# ADS1298_2.net
KiCad netlist of a schematic drawn in Altium Designer
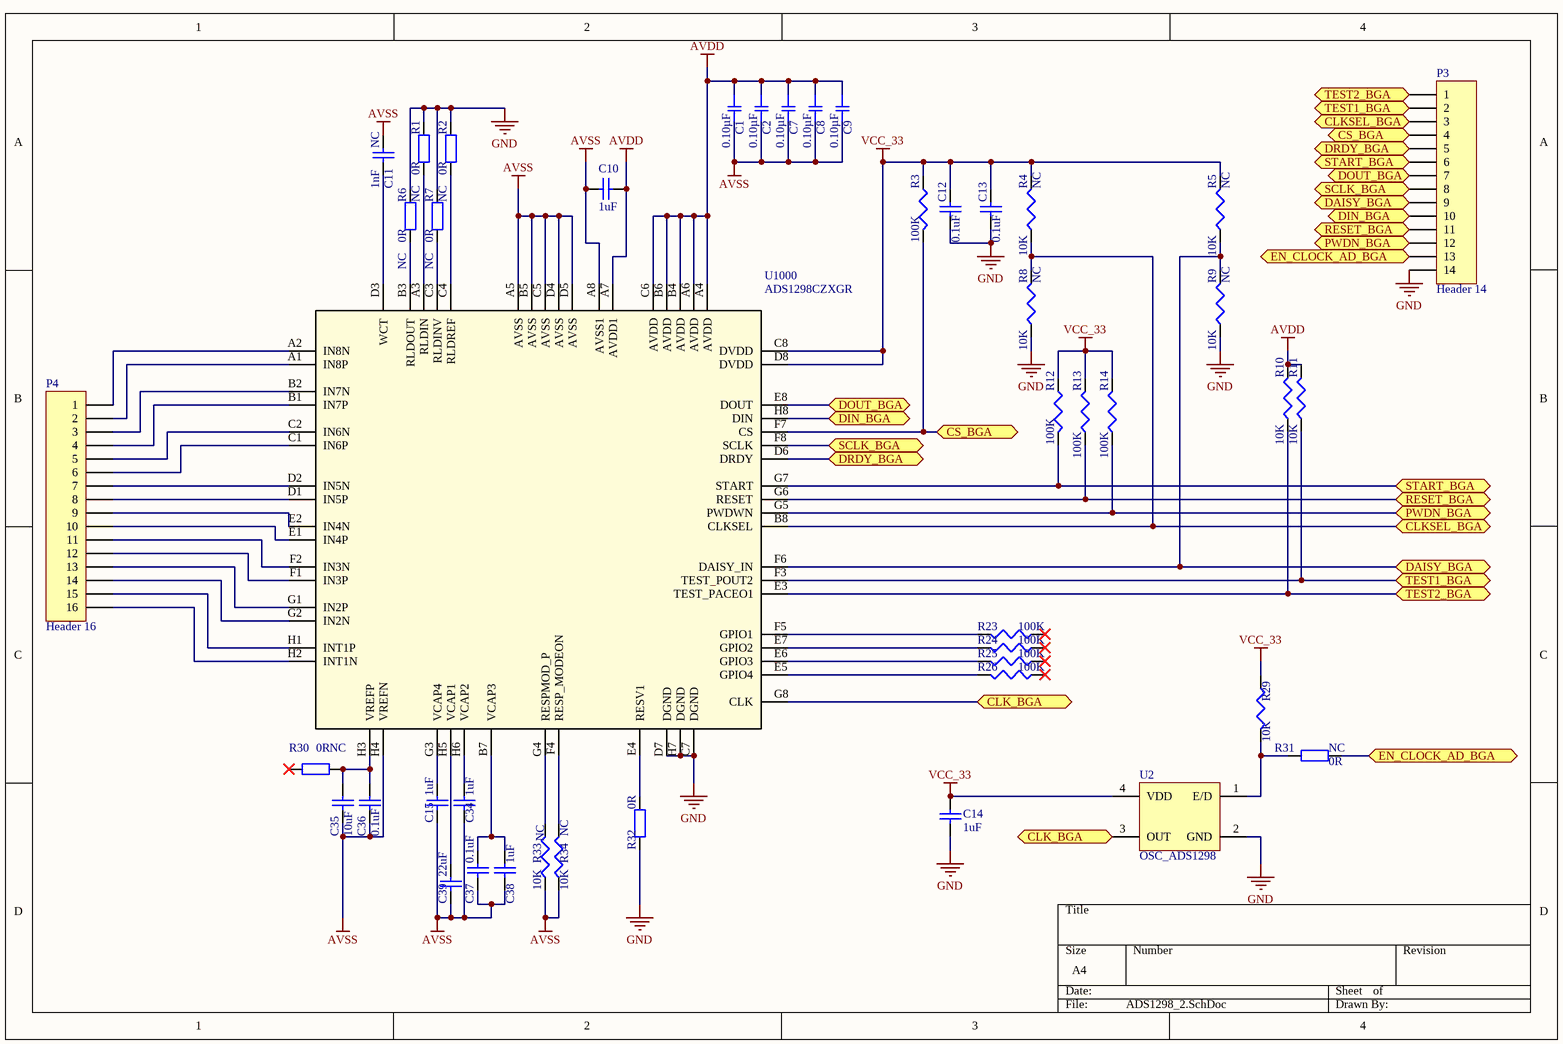
[diagram p0: ADS1298_2.SchDoc]

(export (version "E")
  (design (tool "Eeschema 10.0.6"))
  (components
    (comp (ref "C1")
      (value "0.10µF")
      (footprint "SMD-0201C")
      (description "CAP CER 0.1UF 10V X6S 0201")
      (fields
        (field (name "DIGI-KEY PART NUMBER") "490-12232-1-ND")
        (field (name "PART NUMBER") "GRT033C81A104KE01D")
      )
      (libsource (lib "capacitor_murata_0201") (part "GRT033C81A104KE01D"))
    )
    (comp (ref "C2")
      (value "0.10µF")
      (footprint "SMD-0201C")
      (description "CAP CER 0.1UF 10V X6S 0201")
      (fields
        (field (name "DIGI-KEY PART NUMBER") "490-12232-1-ND")
        (field (name "PART NUMBER") "GRT033C81A104KE01D")
      )
      (libsource (lib "capacitor_murata_0201") (part "GRT033C81A104KE01D"))
    )
    (comp (ref "C7")
      (value "0.10µF")
      (footprint "SMD-0201C")
      (description "CAP CER 0.1UF 10V X6S 0201")
      (fields
        (field (name "DIGI-KEY PART NUMBER") "490-12232-1-ND")
        (field (name "PART NUMBER") "GRT033C81A104KE01D")
      )
      (libsource (lib "capacitor_murata_0201") (part "GRT033C81A104KE01D"))
    )
    (comp (ref "C8")
      (value "0.10µF")
      (footprint "SMD-0201C")
      (description "CAP CER 0.1UF 10V X6S 0201")
      (fields
        (field (name "DIGI-KEY PART NUMBER") "490-12232-1-ND")
        (field (name "PART NUMBER") "GRT033C81A104KE01D")
      )
      (libsource (lib "capacitor_murata_0201") (part "GRT033C81A104KE01D"))
    )
    (comp (ref "C9")
      (value "0.10µF")
      (footprint "SMD-0201C")
      (description "CAP CER 0.1UF 10V X6S 0201")
      (fields
        (field (name "DIGI-KEY PART NUMBER") "490-12232-1-ND")
        (field (name "PART NUMBER") "GRT033C81A104KE01D")
      )
      (libsource (lib "capacitor_murata_0201") (part "GRT033C81A104KE01D"))
    )
    (comp (ref "C10")
      (value "1uF")
      (footprint "cap_0402_R - modified")
      (description "Capacitor")
      (fields (field (name "Comment") "Cap") (field (name "PUBLISHER") "Altium Limited"))
      (libsource (lib "Miscellaneous Devices") (part "Cap"))
    )
    (comp (ref "C11")
      (value "NC")
      (footprint "cap_0402_R - modified")
      (description "Capacitor")
      (fields (field (name "ALTIUM_VALUE") "1nF") (field (name "PUBLISHER") "Altium Limited"))
      (libsource (lib "Miscellaneous Devices") (part "Cap"))
    )
    (comp (ref "C12")
      (value "0.1uF")
      (footprint "cap_0402_R - modified")
      (description "Capacitor")
      (fields (field (name "Comment") "Cap") (field (name "PUBLISHER") "Altium Limited"))
      (libsource (lib "Miscellaneous Devices") (part "Cap"))
    )
    (comp (ref "C13")
      (value "0.1uF")
      (footprint "cap_0402_R - modified")
      (description "Capacitor")
      (fields (field (name "Comment") "Cap") (field (name "PUBLISHER") "Altium Limited"))
      (libsource (lib "Miscellaneous Devices") (part "Cap"))
    )
    (comp (ref "C14")
      (value "1uF")
      (footprint "cap_0402_R - modified")
      (description "Capacitor")
      (fields (field (name "Comment") "Cap") (field (name "PUBLISHER") "Altium Limited"))
      (libsource (lib "Miscellaneous Devices") (part "Cap"))
    )
    (comp (ref "C15")
      (value "1uF")
      (footprint "cap_0402_R - modified")
      (description "Capacitor")
      (fields (field (name "Comment") "Cap") (field (name "PUBLISHER") "Altium Limited"))
      (libsource (lib "Miscellaneous Devices") (part "Cap"))
    )
    (comp (ref "C34")
      (value "1uF")
      (footprint "cap_0402_R - modified")
      (description "Capacitor")
      (fields (field (name "Comment") "Cap") (field (name "PUBLISHER") "Altium Limited"))
      (libsource (lib "Miscellaneous Devices") (part "Cap"))
    )
    (comp (ref "C35")
      (value "10uF")
      (footprint "cap_0402_R - modified")
      (description "Capacitor")
      (fields (field (name "Comment") "Cap") (field (name "PUBLISHER") "Altium Limited"))
      (libsource (lib "Miscellaneous Devices") (part "Cap"))
    )
    (comp (ref "C36")
      (value "0.1uF")
      (footprint "cap_0402_R - modified")
      (description "Capacitor")
      (fields (field (name "Comment") "Cap") (field (name "PUBLISHER") "Altium Limited"))
      (libsource (lib "Miscellaneous Devices") (part "Cap"))
    )
    (comp (ref "C37")
      (value "0.1uF")
      (footprint "cap_0402_R - modified")
      (description "Capacitor")
      (fields (field (name "Comment") "Cap") (field (name "PUBLISHER") "Altium Limited"))
      (libsource (lib "Miscellaneous Devices") (part "Cap"))
    )
    (comp (ref "C38")
      (value "1uF")
      (footprint "cap_0402_R - modified")
      (description "Capacitor")
      (fields (field (name "Comment") "Cap") (field (name "PUBLISHER") "Altium Limited"))
      (libsource (lib "Miscellaneous Devices") (part "Cap"))
    )
    (comp (ref "C39")
      (value "22uF")
      (footprint "cap_0402_R - modified")
      (description "Capacitor")
      (fields (field (name "Comment") "Cap") (field (name "PUBLISHER") "Altium Limited"))
      (libsource (lib "Miscellaneous Devices") (part "Cap"))
    )
    (comp (ref "P3")
      (value "Header 14")
      (footprint "61301421121")
      (description "Header, 14-Pin")
      (fields (field (name "PUBLISHER") "Altium Limited"))
      (libsource (lib "Miscellaneous Connectors") (part "Header 14"))
    )
    (comp (ref "P4")
      (value "Header 16")
      (footprint "61301621121")
      (description "Header, 16-Pin")
      (fields (field (name "PUBLISHER") "Altium Limited"))
      (libsource (lib "Miscellaneous Connectors") (part "Header 16"))
    )
    (comp (ref "R1")
      (value "NC")
      (footprint "cap_0402_R - modified")
      (description "Resistor")
      (fields (field (name "ALTIUM_VALUE") "0R") (field (name "PUBLISHER") "Altium Limited"))
      (libsource (lib "Miscellaneous Devices") (part "Res2"))
    )
    (comp (ref "R2")
      (value "NC")
      (footprint "cap_0402_R - modified")
      (description "Resistor")
      (fields (field (name "ALTIUM_VALUE") "0R") (field (name "PUBLISHER") "Altium Limited"))
      (libsource (lib "Miscellaneous Devices") (part "Res2"))
    )
    (comp (ref "R3")
      (value "100K")
      (footprint "res_0402_R - modified")
      (description "Resistor")
      (fields (field (name "Comment") "Res3") (field (name "PUBLISHER") "Altium Limited"))
      (libsource (lib "Miscellaneous Devices") (part "Res3"))
    )
    (comp (ref "R4")
      (value "NC")
      (footprint "cap_0402_R - modified")
      (description "Resistor")
      (fields (field (name "ALTIUM_VALUE") "10K") (field (name "PUBLISHER") "Altium Limited"))
      (libsource (lib "Miscellaneous Devices") (part "Res3"))
    )
    (comp (ref "R5")
      (value "NC")
      (footprint "cap_0402_R - modified")
      (description "Resistor")
      (fields (field (name "ALTIUM_VALUE") "10K") (field (name "PUBLISHER") "Altium Limited"))
      (libsource (lib "Miscellaneous Devices") (part "Res3"))
    )
    (comp (ref "R6")
      (value "NC")
      (footprint "cap_0402_R - modified")
      (description "Resistor")
      (fields (field (name "ALTIUM_VALUE") "0R") (field (name "PUBLISHER") "Altium Limited"))
      (libsource (lib "Miscellaneous Devices") (part "Res2"))
    )
    (comp (ref "R7")
      (value "NC")
      (footprint "cap_0402_R - modified")
      (description "Resistor")
      (fields (field (name "ALTIUM_VALUE") "0R") (field (name "PUBLISHER") "Altium Limited"))
      (libsource (lib "Miscellaneous Devices") (part "Res2"))
    )
    (comp (ref "R8")
      (value "NC")
      (footprint "cap_0402_R - modified")
      (description "Resistor")
      (fields (field (name "ALTIUM_VALUE") "10K") (field (name "PUBLISHER") "Altium Limited"))
      (libsource (lib "Miscellaneous Devices") (part "Res3"))
    )
    (comp (ref "R9")
      (value "NC")
      (footprint "cap_0402_R - modified")
      (description "Resistor")
      (fields (field (name "ALTIUM_VALUE") "10K") (field (name "PUBLISHER") "Altium Limited"))
      (libsource (lib "Miscellaneous Devices") (part "Res3"))
    )
    (comp (ref "R10")
      (value "10K")
      (footprint "cap_0402_R - modified")
      (description "Resistor")
      (fields (field (name "PUBLISHER") "Altium Limited"))
      (libsource (lib "Miscellaneous Devices") (part "Res3"))
    )
    (comp (ref "R11")
      (value "10K")
      (footprint "cap_0402_R - modified")
      (description "Resistor")
      (fields (field (name "PUBLISHER") "Altium Limited"))
      (libsource (lib "Miscellaneous Devices") (part "Res3"))
    )
    (comp (ref "R12")
      (value "100K")
      (footprint "res_0402_R - modified")
      (description "Resistor")
      (fields (field (name "Comment") "Res3") (field (name "PUBLISHER") "Altium Limited"))
      (libsource (lib "Miscellaneous Devices") (part "Res3"))
    )
    (comp (ref "R13")
      (value "100K")
      (footprint "res_0402_R - modified")
      (description "Resistor")
      (fields (field (name "Comment") "Res3") (field (name "PUBLISHER") "Altium Limited"))
      (libsource (lib "Miscellaneous Devices") (part "Res3"))
    )
    (comp (ref "R14")
      (value "100K")
      (footprint "res_0402_R - modified")
      (description "Resistor")
      (fields (field (name "Comment") "Res3") (field (name "PUBLISHER") "Altium Limited"))
      (libsource (lib "Miscellaneous Devices") (part "Res3"))
    )
    (comp (ref "R23")
      (value "100K")
      (footprint "res_0402_R - modified")
      (description "Resistor")
      (fields (field (name "Comment") "Res3") (field (name "PUBLISHER") "Altium Limited"))
      (libsource (lib "Miscellaneous Devices") (part "Res3"))
    )
    (comp (ref "R24")
      (value "100K")
      (footprint "res_0402_R - modified")
      (description "Resistor")
      (fields (field (name "Comment") "Res3") (field (name "PUBLISHER") "Altium Limited"))
      (libsource (lib "Miscellaneous Devices") (part "Res3"))
    )
    (comp (ref "R25")
      (value "100K")
      (footprint "res_0402_R - modified")
      (description "Resistor")
      (fields (field (name "Comment") "Res3") (field (name "PUBLISHER") "Altium Limited"))
      (libsource (lib "Miscellaneous Devices") (part "Res3"))
    )
    (comp (ref "R26")
      (value "100K")
      (footprint "res_0402_R - modified")
      (description "Resistor")
      (fields (field (name "Comment") "Res3") (field (name "PUBLISHER") "Altium Limited"))
      (libsource (lib "Miscellaneous Devices") (part "Res3"))
    )
    (comp (ref "R29")
      (value "10K")
      (footprint "res_0402_R - modified")
      (description "Resistor")
      (fields (field (name "Comment") "Res3") (field (name "PUBLISHER") "Altium Limited"))
      (libsource (lib "Miscellaneous Devices") (part "Res3"))
    )
    (comp (ref "R30")
      (value "NC")
      (footprint "cap_0402_R - modified")
      (description "Resistor")
      (fields (field (name "ALTIUM_VALUE") "0R") (field (name "PUBLISHER") "Altium Limited"))
      (libsource (lib "") (part "Res2_2"))
    )
    (comp (ref "R31")
      (value "NC")
      (footprint "cap_0402_R - modified")
      (description "Resistor")
      (fields (field (name "ALTIUM_VALUE") "0R") (field (name "PUBLISHER") "Altium Limited"))
      (libsource (lib "") (part "Res2_1"))
    )
    (comp (ref "R32")
      (value "0R")
      (footprint "cap_0402_R - modified")
      (description "Resistor")
      (fields (field (name "PUBLISHER") "Altium Limited"))
      (libsource (lib "Miscellaneous Devices") (part "Res2"))
    )
    (comp (ref "R33")
      (value "NC")
      (footprint "cap_0402_R - modified")
      (description "Resistor")
      (fields (field (name "ALTIUM_VALUE") "10K") (field (name "PUBLISHER") "Altium Limited"))
      (libsource (lib "Miscellaneous Devices") (part "Res3"))
    )
    (comp (ref "R34")
      (value "NC")
      (footprint "res_0402_R - modified")
      (description "Resistor")
      (fields (field (name "ALTIUM_VALUE") "10K") (field (name "PUBLISHER") "Altium Limited"))
      (libsource (lib "Miscellaneous Devices") (part "Res3"))
    )
    (comp (ref "U2")
      (value "OSC_ADS1298")
      (footprint "HC735 - OSC ADS1298")
      (description "Linear Regulator")
      (libsource (lib "Demo_Board_library_SCH") (part "OSC_ADS1298"))
    )
    (comp (ref "U1000")
      (value "ADS1298CZXGR")
      (footprint "BGA64C80P8X8_800X800X106")
      (description "8-Channel, 24-Bit Analog-To-Digital Converter With Integrated ECG Front End")
      (fields
        (field (name "MANUFACTURER") "Texas Instruments")
        (field (name "GENERIC_PART_NUMBER") "ADS1298")
        (field (name "COPYRIGHT") "Copyright (C) 2018 Accelerated Designs. All rights reserved")
      )
      (libsource (lib "2020-06-18_08-38-23") (part "ADS1298CZXGR"))
    )
  )
  (nets
    (net (code "1") (name "/CLKSEL_BGA") (class "Default")
      (node (ref "P3") (pin "3") (pinfunction "3_3") (pintype "passive"))
      (node (ref "R4") (pin "1") (pinfunction "1_1") (pintype "passive"))
      (node (ref "R8") (pin "2") (pinfunction "2_2") (pintype "passive"))
      (node (ref "U1000") (pin "B8") (pinfunction "CLKSEL_B8") (pintype "passive"))
    )
    (net (code "2") (name "/CLK_BGA") (class "Default")
      (node (ref "U1000") (pin "G8") (pinfunction "CLK_G8") (pintype "passive"))
      (node (ref "U2") (pin "3") (pinfunction "OUT_3") (pintype "passive"))
    )
    (net (code "3") (name "/CS_BGA") (class "Default")
      (node (ref "P3") (pin "4") (pinfunction "4_4") (pintype "passive"))
      (node (ref "R3") (pin "2") (pinfunction "2_2") (pintype "passive"))
      (node (ref "U1000") (pin "F7") (pinfunction "CS_F7") (pintype "passive"))
    )
    (net (code "4") (name "/DAISY_BGA") (class "Default")
      (node (ref "P3") (pin "9") (pinfunction "9_9") (pintype "passive"))
      (node (ref "R5") (pin "1") (pinfunction "1_1") (pintype "passive"))
      (node (ref "R9") (pin "2") (pinfunction "2_2") (pintype "passive"))
      (node (ref "U1000") (pin "F6") (pinfunction "DAISY_IN_F6") (pintype "passive"))
    )
    (net (code "5") (name "/DIN_BGA") (class "Default")
      (node (ref "P3") (pin "10") (pinfunction "10_10") (pintype "passive"))
      (node (ref "U1000") (pin "H8") (pinfunction "DIN_H8") (pintype "passive"))
    )
    (net (code "6") (name "/DOUT_BGA") (class "Default")
      (node (ref "P3") (pin "7") (pinfunction "7_7") (pintype "passive"))
      (node (ref "U1000") (pin "E8") (pinfunction "DOUT_E8") (pintype "passive"))
    )
    (net (code "7") (name "/DRDY_BGA") (class "Default")
      (node (ref "P3") (pin "5") (pinfunction "5_5") (pintype "passive"))
      (node (ref "U1000") (pin "D6") (pinfunction "DRDY_D6") (pintype "passive"))
    )
    (net (code "8") (name "/EN_CLOCK_AD_BGA") (class "Default")
      (node (ref "P3") (pin "13") (pinfunction "13_13") (pintype "passive"))
      (node (ref "R31") (pin "1") (pinfunction "1_1") (pintype "passive"))
    )
    (net (code "9") (name "/PWDN_BGA") (class "Default")
      (node (ref "P3") (pin "12") (pinfunction "12_12") (pintype "passive"))
      (node (ref "R14") (pin "1") (pinfunction "1_1") (pintype "passive"))
      (node (ref "U1000") (pin "G5") (pinfunction "PWDWN_G5") (pintype "passive"))
    )
    (net (code "10") (name "/RESET_BGA") (class "Default")
      (node (ref "P3") (pin "11") (pinfunction "11_11") (pintype "passive"))
      (node (ref "R13") (pin "1") (pinfunction "1_1") (pintype "passive"))
      (node (ref "U1000") (pin "G6") (pinfunction "RESET_G6") (pintype "passive"))
    )
    (net (code "11") (name "/SCLK_BGA") (class "Default")
      (node (ref "P3") (pin "8") (pinfunction "8_8") (pintype "passive"))
      (node (ref "U1000") (pin "F8") (pinfunction "SCLK_F8") (pintype "passive"))
    )
    (net (code "12") (name "/START_BGA") (class "Default")
      (node (ref "P3") (pin "6") (pinfunction "6_6") (pintype "passive"))
      (node (ref "R12") (pin "2") (pinfunction "2_2") (pintype "passive"))
      (node (ref "U1000") (pin "G7") (pinfunction "START_G7") (pintype "passive"))
    )
    (net (code "13") (name "/TEST1_BGA") (class "Default")
      (node (ref "P3") (pin "2") (pinfunction "2_2") (pintype "passive"))
      (node (ref "R11") (pin "1") (pinfunction "1_1") (pintype "passive"))
      (node (ref "U1000") (pin "F3") (pinfunction "TEST_POUT2_F3") (pintype "passive"))
    )
    (net (code "14") (name "/TEST2_BGA") (class "Default")
      (node (ref "P3") (pin "1") (pinfunction "1_1") (pintype "passive"))
      (node (ref "R10") (pin "1") (pinfunction "1_1") (pintype "passive"))
      (node (ref "U1000") (pin "E3") (pinfunction "TEST_PACEO1_E3") (pintype "passive"))
    )
    (net (code "15") (name "AVDD") (class "Default")
      (node (ref "C1") (pin "1") (pinfunction "1_1") (pintype "passive"))
      (node (ref "C10") (pin "1") (pinfunction "1_1") (pintype "passive"))
      (node (ref "C2") (pin "1") (pinfunction "1_1") (pintype "passive"))
      (node (ref "C7") (pin "1") (pinfunction "1_1") (pintype "passive"))
      (node (ref "C8") (pin "1") (pinfunction "1_1") (pintype "passive"))
      (node (ref "C9") (pin "1") (pinfunction "1_1") (pintype "passive"))
      (node (ref "R10") (pin "2") (pinfunction "2_2") (pintype "passive"))
      (node (ref "R11") (pin "2") (pinfunction "2_2") (pintype "passive"))
      (node (ref "U1000") (pin "A4") (pinfunction "AVDD_A4") (pintype "passive"))
      (node (ref "U1000") (pin "A6") (pinfunction "AVDD_A6") (pintype "passive"))
      (node (ref "U1000") (pin "A7") (pinfunction "AVDD1_A7") (pintype "passive"))
      (node (ref "U1000") (pin "B4") (pinfunction "AVDD_B4") (pintype "passive"))
      (node (ref "U1000") (pin "B6") (pinfunction "AVDD_B6") (pintype "passive"))
      (node (ref "U1000") (pin "C6") (pinfunction "AVDD_C6") (pintype "passive"))
    )
    (net (code "16") (name "AVSS") (class "Default")
      (node (ref "C1") (pin "2") (pinfunction "2_2") (pintype "passive"))
      (node (ref "C10") (pin "2") (pinfunction "2_2") (pintype "passive"))
      (node (ref "C11") (pin "1") (pinfunction "1_1") (pintype "passive"))
      (node (ref "C15") (pin "1") (pinfunction "1_1") (pintype "passive"))
      (node (ref "C2") (pin "2") (pinfunction "2_2") (pintype "passive"))
      (node (ref "C34") (pin "1") (pinfunction "1_1") (pintype "passive"))
      (node (ref "C35") (pin "1") (pinfunction "1_1") (pintype "passive"))
      (node (ref "C36") (pin "1") (pinfunction "1_1") (pintype "passive"))
      (node (ref "C37") (pin "1") (pinfunction "1_1") (pintype "passive"))
      (node (ref "C38") (pin "1") (pinfunction "1_1") (pintype "passive"))
      (node (ref "C39") (pin "1") (pinfunction "1_1") (pintype "passive"))
      (node (ref "C7") (pin "2") (pinfunction "2_2") (pintype "passive"))
      (node (ref "C8") (pin "2") (pinfunction "2_2") (pintype "passive"))
      (node (ref "C9") (pin "2") (pinfunction "2_2") (pintype "passive"))
      (node (ref "R33") (pin "1") (pinfunction "1_1") (pintype "passive"))
      (node (ref "R34") (pin "1") (pinfunction "1_1") (pintype "passive"))
      (node (ref "U1000") (pin "A5") (pinfunction "AVSS_A5") (pintype "passive"))
      (node (ref "U1000") (pin "A8") (pinfunction "AVSS1_A8") (pintype "passive"))
      (node (ref "U1000") (pin "B5") (pinfunction "AVSS_B5") (pintype "passive"))
      (node (ref "U1000") (pin "C5") (pinfunction "AVSS_C5") (pintype "passive"))
      (node (ref "U1000") (pin "D4") (pinfunction "AVSS_D4") (pintype "passive"))
      (node (ref "U1000") (pin "D5") (pinfunction "AVSS_D5") (pintype "passive"))
      (node (ref "U1000") (pin "H4") (pinfunction "VREFN_H4") (pintype "passive"))
    )
    (net (code "17") (name "GND") (class "Default")
      (node (ref "C12") (pin "1") (pinfunction "1_1") (pintype "passive"))
      (node (ref "C13") (pin "1") (pinfunction "1_1") (pintype "passive"))
      (node (ref "C14") (pin "2") (pinfunction "2_2") (pintype "passive"))
      (node (ref "P3") (pin "14") (pinfunction "14_14") (pintype "passive"))
      (node (ref "R1") (pin "1") (pinfunction "1_1") (pintype "passive"))
      (node (ref "R2") (pin "1") (pinfunction "1_1") (pintype "passive"))
      (node (ref "R32") (pin "2") (pinfunction "2_2") (pintype "passive"))
      (node (ref "R6") (pin "1") (pinfunction "1_1") (pintype "passive"))
      (node (ref "R7") (pin "1") (pinfunction "1_1") (pintype "passive"))
      (node (ref "R8") (pin "1") (pinfunction "1_1") (pintype "passive"))
      (node (ref "R9") (pin "1") (pinfunction "1_1") (pintype "passive"))
      (node (ref "U1000") (pin "C7") (pinfunction "DGND_C7") (pintype "passive"))
      (node (ref "U1000") (pin "D7") (pinfunction "DGND_D7") (pintype "passive"))
      (node (ref "U1000") (pin "H7") (pinfunction "DGND_H7") (pintype "passive"))
      (node (ref "U2") (pin "2") (pinfunction "GND_2") (pintype "passive"))
    )
    (net (code "18") (name "Net-(U2-E{slash}D)") (class "Default")
      (node (ref "R29") (pin "2") (pinfunction "2_2") (pintype "passive"))
      (node (ref "R31") (pin "2") (pinfunction "2_2") (pintype "passive"))
      (node (ref "U2") (pin "1") (pinfunction "E/D_1") (pintype "passive"))
    )
    (net (code "19") (name "Net-(U1000-GPIO1)") (class "Default")
      (node (ref "R23") (pin "2") (pinfunction "2_2") (pintype "passive"))
      (node (ref "U1000") (pin "F5") (pinfunction "GPIO1_F5") (pintype "passive"))
    )
    (net (code "20") (name "Net-(U1000-GPIO2)") (class "Default")
      (node (ref "R24") (pin "2") (pinfunction "2_2") (pintype "passive"))
      (node (ref "U1000") (pin "E7") (pinfunction "GPIO2_E7") (pintype "passive"))
    )
    (net (code "21") (name "Net-(U1000-GPIO3)") (class "Default")
      (node (ref "R25") (pin "2") (pinfunction "2_2") (pintype "passive"))
      (node (ref "U1000") (pin "E6") (pinfunction "GPIO3_E6") (pintype "passive"))
    )
    (net (code "22") (name "Net-(U1000-GPIO4)") (class "Default")
      (node (ref "R26") (pin "2") (pinfunction "2_2") (pintype "passive"))
      (node (ref "U1000") (pin "E5") (pinfunction "GPIO4_E5") (pintype "passive"))
    )
    (net (code "23") (name "Net-(U1000-IN2N)") (class "Default")
      (node (ref "P4") (pin "14") (pinfunction "14_14") (pintype "passive"))
      (node (ref "U1000") (pin "G2") (pinfunction "IN2N_G2") (pintype "passive"))
    )
    (net (code "24") (name "Net-(U1000-IN2P)") (class "Default")
      (node (ref "P4") (pin "13") (pinfunction "13_13") (pintype "passive"))
      (node (ref "U1000") (pin "G1") (pinfunction "IN2P_G1") (pintype "passive"))
    )
    (net (code "25") (name "Net-(U1000-IN3N)") (class "Default")
      (node (ref "P4") (pin "11") (pinfunction "11_11") (pintype "passive"))
      (node (ref "U1000") (pin "F2") (pinfunction "IN3N_F2") (pintype "passive"))
    )
    (net (code "26") (name "Net-(U1000-IN3P)") (class "Default")
      (node (ref "P4") (pin "12") (pinfunction "12_12") (pintype "passive"))
      (node (ref "U1000") (pin "F1") (pinfunction "IN3P_F1") (pintype "passive"))
    )
    (net (code "27") (name "Net-(U1000-IN4N)") (class "Default")
      (node (ref "P4") (pin "9") (pinfunction "9_9") (pintype "passive"))
      (node (ref "U1000") (pin "E2") (pinfunction "IN4N_E2") (pintype "passive"))
    )
    (net (code "28") (name "Net-(U1000-IN4P)") (class "Default")
      (node (ref "P4") (pin "10") (pinfunction "10_10") (pintype "passive"))
      (node (ref "U1000") (pin "E1") (pinfunction "IN4P_E1") (pintype "passive"))
    )
    (net (code "29") (name "Net-(U1000-IN5N)") (class "Default")
      (node (ref "P4") (pin "7") (pinfunction "7_7") (pintype "passive"))
      (node (ref "U1000") (pin "D2") (pinfunction "IN5N_D2") (pintype "passive"))
    )
    (net (code "30") (name "Net-(U1000-IN5P)") (class "Default")
      (node (ref "P4") (pin "8") (pinfunction "8_8") (pintype "passive"))
      (node (ref "U1000") (pin "D1") (pinfunction "IN5P_D1") (pintype "passive"))
    )
    (net (code "31") (name "Net-(U1000-IN6N)") (class "Default")
      (node (ref "P4") (pin "5") (pinfunction "5_5") (pintype "passive"))
      (node (ref "U1000") (pin "C2") (pinfunction "IN6N_C2") (pintype "passive"))
    )
    (net (code "32") (name "Net-(U1000-IN6P)") (class "Default")
      (node (ref "P4") (pin "6") (pinfunction "6_6") (pintype "passive"))
      (node (ref "U1000") (pin "C1") (pinfunction "IN6P_C1") (pintype "passive"))
    )
    (net (code "33") (name "Net-(U1000-IN7N)") (class "Default")
      (node (ref "P4") (pin "3") (pinfunction "3_3") (pintype "passive"))
      (node (ref "U1000") (pin "B2") (pinfunction "IN7N_B2") (pintype "passive"))
    )
    (net (code "34") (name "Net-(U1000-IN7P)") (class "Default")
      (node (ref "P4") (pin "4") (pinfunction "4_4") (pintype "passive"))
      (node (ref "U1000") (pin "B1") (pinfunction "IN7P_B1") (pintype "passive"))
    )
    (net (code "35") (name "Net-(U1000-IN8N)") (class "Default")
      (node (ref "P4") (pin "1") (pinfunction "1_1") (pintype "passive"))
      (node (ref "U1000") (pin "A2") (pinfunction "IN8N_A2") (pintype "passive"))
    )
    (net (code "36") (name "Net-(U1000-IN8P)") (class "Default")
      (node (ref "P4") (pin "2") (pinfunction "2_2") (pintype "passive"))
      (node (ref "U1000") (pin "A1") (pinfunction "IN8P_A1") (pintype "passive"))
    )
    (net (code "37") (name "Net-(U1000-INT1N)") (class "Default")
      (node (ref "P4") (pin "16") (pinfunction "16_16") (pintype "passive"))
      (node (ref "U1000") (pin "H2") (pinfunction "INT1N_H2") (pintype "passive"))
    )
    (net (code "38") (name "Net-(U1000-INT1P)") (class "Default")
      (node (ref "P4") (pin "15") (pinfunction "15_15") (pintype "passive"))
      (node (ref "U1000") (pin "H1") (pinfunction "INT1P_H1") (pintype "passive"))
    )
    (net (code "39") (name "Net-(U1000-RESPMOD_P)") (class "Default")
      (node (ref "R33") (pin "2") (pinfunction "2_2") (pintype "passive"))
      (node (ref "U1000") (pin "G4") (pinfunction "RESPMOD_P_G4") (pintype "passive"))
    )
    (net (code "40") (name "Net-(U1000-RESP_MODEON)") (class "Default")
      (node (ref "R34") (pin "2") (pinfunction "2_2") (pintype "passive"))
      (node (ref "U1000") (pin "F4") (pinfunction "RESP_MODEON_F4") (pintype "passive"))
    )
    (net (code "41") (name "Net-(U1000-RESV1)") (class "Default")
      (node (ref "R32") (pin "1") (pinfunction "1_1") (pintype "passive"))
      (node (ref "U1000") (pin "E4") (pinfunction "RESV1_E4") (pintype "passive"))
    )
    (net (code "42") (name "Net-(U1000-RLDIN)") (class "Default")
      (node (ref "R1") (pin "2") (pinfunction "2_2") (pintype "passive"))
      (node (ref "U1000") (pin "A3") (pinfunction "RLDIN_A3") (pintype "passive"))
    )
    (net (code "43") (name "Net-(U1000-RLDINV)") (class "Default")
      (node (ref "R7") (pin "2") (pinfunction "2_2") (pintype "passive"))
      (node (ref "U1000") (pin "C3") (pinfunction "RLDINV_C3") (pintype "passive"))
    )
    (net (code "44") (name "Net-(U1000-RLDOUT)") (class "Default")
      (node (ref "R6") (pin "2") (pinfunction "2_2") (pintype "passive"))
      (node (ref "U1000") (pin "B3") (pinfunction "RLDOUT_B3") (pintype "passive"))
    )
    (net (code "45") (name "Net-(U1000-RLDREF)") (class "Default")
      (node (ref "R2") (pin "2") (pinfunction "2_2") (pintype "passive"))
      (node (ref "U1000") (pin "C4") (pinfunction "RLDREF_C4") (pintype "passive"))
    )
    (net (code "46") (name "Net-(U1000-VCAP1)") (class "Default")
      (node (ref "C39") (pin "2") (pinfunction "2_2") (pintype "passive"))
      (node (ref "U1000") (pin "H5") (pinfunction "VCAP1_H5") (pintype "passive"))
    )
    (net (code "47") (name "Net-(U1000-VCAP2)") (class "Default")
      (node (ref "C34") (pin "2") (pinfunction "2_2") (pintype "passive"))
      (node (ref "U1000") (pin "H6") (pinfunction "VCAP2_H6") (pintype "passive"))
    )
    (net (code "48") (name "Net-(U1000-VCAP3)") (class "Default")
      (node (ref "C37") (pin "2") (pinfunction "2_2") (pintype "passive"))
      (node (ref "C38") (pin "2") (pinfunction "2_2") (pintype "passive"))
      (node (ref "U1000") (pin "B7") (pinfunction "VCAP3_B7") (pintype "passive"))
    )
    (net (code "49") (name "Net-(U1000-VCAP4)") (class "Default")
      (node (ref "C15") (pin "2") (pinfunction "2_2") (pintype "passive"))
      (node (ref "U1000") (pin "G3") (pinfunction "VCAP4_G3") (pintype "passive"))
    )
    (net (code "50") (name "Net-(U1000-VREFP)") (class "Default")
      (node (ref "C35") (pin "2") (pinfunction "2_2") (pintype "passive"))
      (node (ref "C36") (pin "2") (pinfunction "2_2") (pintype "passive"))
      (node (ref "R30") (pin "2") (pinfunction "2_2") (pintype "passive"))
      (node (ref "U1000") (pin "H3") (pinfunction "VREFP_H3") (pintype "passive"))
    )
    (net (code "51") (name "Net-(U1000-WCT)") (class "Default")
      (node (ref "C11") (pin "2") (pinfunction "2_2") (pintype "passive"))
      (node (ref "U1000") (pin "D3") (pinfunction "WCT_D3") (pintype "passive"))
    )
    (net (code "52") (name "VCC_33") (class "Default")
      (node (ref "C12") (pin "2") (pinfunction "2_2") (pintype "passive"))
      (node (ref "C13") (pin "2") (pinfunction "2_2") (pintype "passive"))
      (node (ref "C14") (pin "1") (pinfunction "1_1") (pintype "passive"))
      (node (ref "R12") (pin "1") (pinfunction "1_1") (pintype "passive"))
      (node (ref "R13") (pin "2") (pinfunction "2_2") (pintype "passive"))
      (node (ref "R14") (pin "2") (pinfunction "2_2") (pintype "passive"))
      (node (ref "R29") (pin "1") (pinfunction "1_1") (pintype "passive"))
      (node (ref "R3") (pin "1") (pinfunction "1_1") (pintype "passive"))
      (node (ref "R4") (pin "2") (pinfunction "2_2") (pintype "passive"))
      (node (ref "R5") (pin "2") (pinfunction "2_2") (pintype "passive"))
      (node (ref "U1000") (pin "C8") (pinfunction "DVDD_C8") (pintype "passive"))
      (node (ref "U1000") (pin "D8") (pinfunction "DVDD_D8") (pintype "passive"))
      (node (ref "U2") (pin "4") (pinfunction "VDD_4") (pintype "passive"))
    )
    (net (code "53") (name "unconnected-(R23-Pad1)") (class "Default")
      (node (ref "R23") (pin "1") (pinfunction "1_1") (pintype "passive+no_connect"))
    )
    (net (code "54") (name "unconnected-(R24-Pad1)") (class "Default")
      (node (ref "R24") (pin "1") (pinfunction "1_1") (pintype "passive+no_connect"))
    )
    (net (code "55") (name "unconnected-(R25-Pad1)") (class "Default")
      (node (ref "R25") (pin "1") (pinfunction "1_1") (pintype "passive+no_connect"))
    )
    (net (code "56") (name "unconnected-(R26-Pad1)") (class "Default")
      (node (ref "R26") (pin "1") (pinfunction "1_1") (pintype "passive+no_connect"))
    )
    (net (code "57") (name "unconnected-(R30-Pad1)") (class "Default")
      (node (ref "R30") (pin "1") (pinfunction "1_1") (pintype "passive+no_connect"))
    )
  )
)
